# 8_MGTBank.net
KiCad netlist of a schematic drawn in Altium Designer
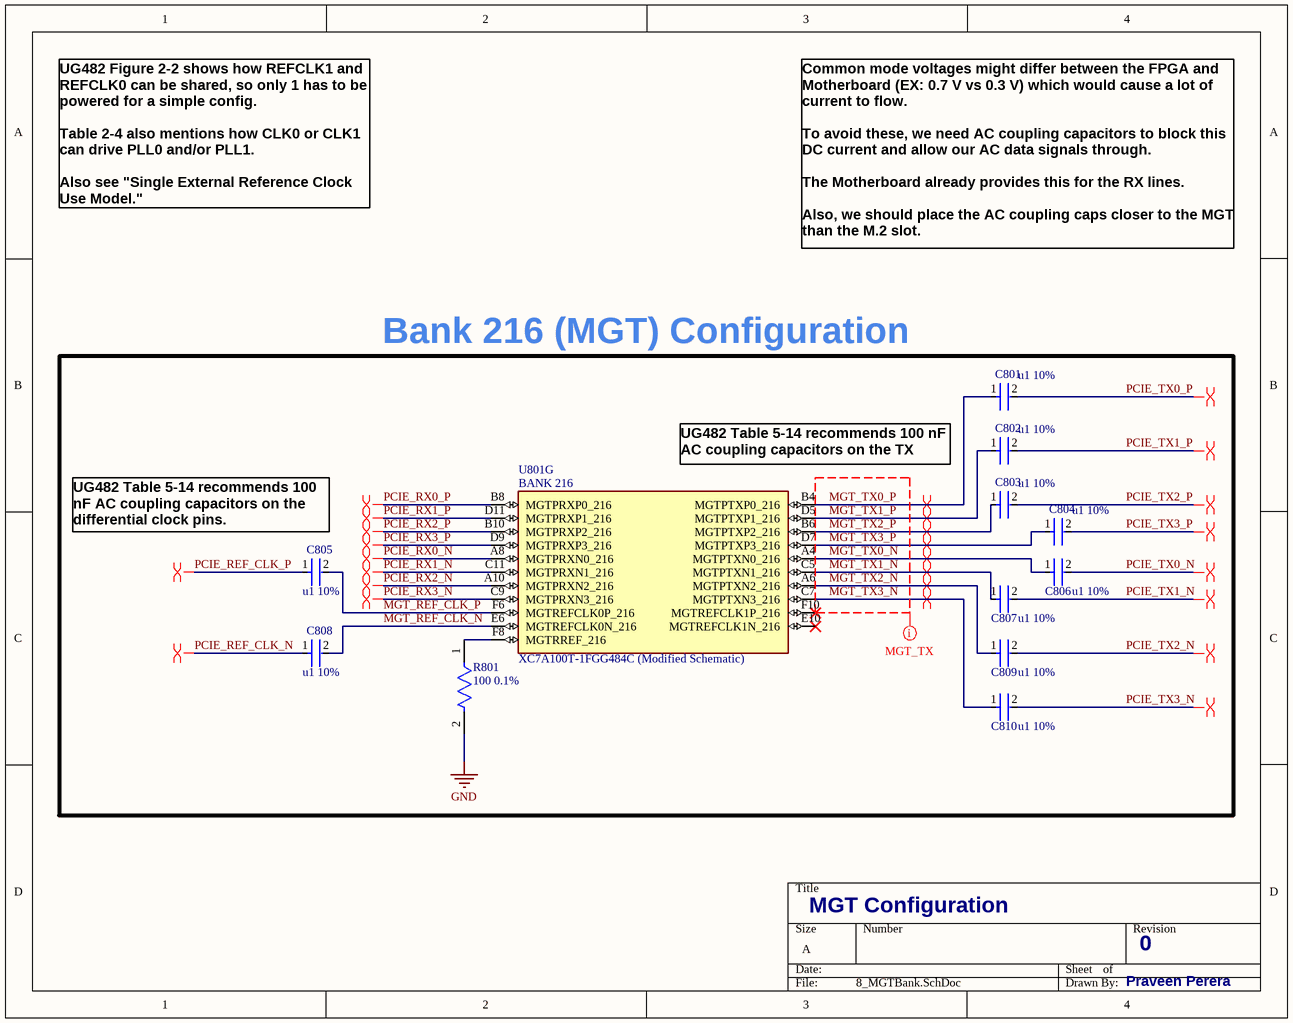
[diagram p0: 8_MGTBank.SchDoc]

(export (version "E")
  (design (tool "Eeschema 10.0.6"))
  (components
    (comp (ref "C801")
      (value "u1 10%")
      (footprint "FP-CL891-IPC_C")
      (description "CL05B104KB5NNNC\r\n\r\nCap Ceramic 100nF 50V X7R ±10% SMD 0402 +125°C Paper T/R")
      (libsource (lib "Altium Content Vault") (part "b4654b650e69147ec39a6b967a45e02"))
    )
    (comp (ref "C802")
      (value "u1 10%")
      (footprint "FP-CL891-IPC_C")
      (description "CL05B104KB5NNNC\r\n\r\nCap Ceramic 100nF 50V X7R ±10% SMD 0402 +125°C Paper T/R")
      (libsource (lib "Altium Content Vault") (part "b4654b650e69147ec39a6b967a45e02"))
    )
    (comp (ref "C803")
      (value "u1 10%")
      (footprint "FP-CL891-IPC_C")
      (description "CL05B104KB5NNNC\r\n\r\nCap Ceramic 100nF 50V X7R ±10% SMD 0402 +125°C Paper T/R")
      (libsource (lib "Altium Content Vault") (part "b4654b650e69147ec39a6b967a45e02"))
    )
    (comp (ref "C804")
      (value "u1 10%")
      (footprint "FP-CL891-IPC_C")
      (description "CL05B104KB5NNNC\r\n\r\nCap Ceramic 100nF 50V X7R ±10% SMD 0402 +125°C Paper T/R")
      (libsource (lib "Altium Content Vault") (part "b4654b650e69147ec39a6b967a45e02"))
    )
    (comp (ref "C805")
      (value "u1 10%")
      (footprint "FP-CL891-IPC_C")
      (description "CL05B104KB5NNNC\r\n\r\nCap Ceramic 100nF 50V X7R ±10% SMD 0402 +125°C Paper T/R")
      (libsource (lib "Altium Content Vault") (part "b4654b650e69147ec39a6b967a45e02"))
    )
    (comp (ref "C806")
      (value "u1 10%")
      (footprint "FP-CL891-IPC_C")
      (description "CL05B104KB5NNNC\r\n\r\nCap Ceramic 100nF 50V X7R ±10% SMD 0402 +125°C Paper T/R")
      (libsource (lib "Altium Content Vault") (part "b4654b650e69147ec39a6b967a45e02"))
    )
    (comp (ref "C807")
      (value "u1 10%")
      (footprint "FP-CL891-IPC_C")
      (description "CL05B104KB5NNNC\r\n\r\nCap Ceramic 100nF 50V X7R ±10% SMD 0402 +125°C Paper T/R")
      (libsource (lib "Altium Content Vault") (part "b4654b650e69147ec39a6b967a45e02"))
    )
    (comp (ref "C808")
      (value "u1 10%")
      (footprint "FP-CL891-IPC_C")
      (description "CL05B104KB5NNNC\r\n\r\nCap Ceramic 100nF 50V X7R ±10% SMD 0402 +125°C Paper T/R")
      (libsource (lib "Altium Content Vault") (part "b4654b650e69147ec39a6b967a45e02"))
    )
    (comp (ref "C809")
      (value "u1 10%")
      (footprint "FP-CL891-IPC_C")
      (description "CL05B104KB5NNNC\r\n\r\nCap Ceramic 100nF 50V X7R ±10% SMD 0402 +125°C Paper T/R")
      (libsource (lib "Altium Content Vault") (part "b4654b650e69147ec39a6b967a45e02"))
    )
    (comp (ref "C810")
      (value "u1 10%")
      (footprint "FP-CL891-IPC_C")
      (description "CL05B104KB5NNNC\r\n\r\nCap Ceramic 100nF 50V X7R ±10% SMD 0402 +125°C Paper T/R")
      (libsource (lib "Altium Content Vault") (part "b4654b650e69147ec39a6b967a45e02"))
    )
    (comp (ref "R801")
      (value "100 0.1%")
      (footprint "FP-ERA1A-IPC_B")
      (description "ERA-1AEB101C\r\n\r\nRES SMD 100 OHM 0.1% 1/20W 0201")
      (fields (field (name "TOLERANCE") "0.1%"))
      (libsource (lib "Altium Content Vault") (part "1029c3af85768c4190bb7ad29bc67b5"))
    )
    (comp (ref "U801")
      (value "XC7A100T-1FGG484C (Modified Schematic)")
      (footprint "BGA484C100P22X22_2300X2300X260N")
      (description "Artix-7 Field Programmable Gate Array (FPGA) IC 285 4976640 101440 484-BBGA")
      (fields (field (name "MP") "XC7A100T-1FGG484C") (field (name "MF") "Xilinx Inc."))
      (libsource (lib "Withanage Perera") (part "XC7A100T-1FGG484C"))
    )
  )
  (nets
    (net (code "1") (name "/MGT_REF_CLK_N") (class "Default")
      (node (ref "C808") (pin "2") (pinfunction "2_2") (pintype "passive"))
      (node (ref "U801") (pin "E6") (pinfunction "MGTREFCLK0N_216_E6") (pintype "bidirectional"))
    )
    (net (code "2") (name "/MGT_REF_CLK_P") (class "Default")
      (node (ref "C805") (pin "2") (pinfunction "2_2") (pintype "passive"))
      (node (ref "U801") (pin "F6") (pinfunction "MGTREFCLK0P_216_F6") (pintype "bidirectional"))
    )
    (net (code "3") (name "/MGT_TX0_N") (class "Default")
      (node (ref "C806") (pin "1") (pinfunction "1_1") (pintype "passive"))
      (node (ref "U801") (pin "A4") (pinfunction "MGTPTXN0_216_A4") (pintype "bidirectional"))
    )
    (net (code "4") (name "/MGT_TX0_P") (class "Default")
      (node (ref "C801") (pin "1") (pinfunction "1_1") (pintype "passive"))
      (node (ref "U801") (pin "B4") (pinfunction "MGTPTXP0_216_B4") (pintype "bidirectional"))
    )
    (net (code "5") (name "/MGT_TX1_N") (class "Default")
      (node (ref "C807") (pin "1") (pinfunction "1_1") (pintype "passive"))
      (node (ref "U801") (pin "C5") (pinfunction "MGTPTXN1_216_C5") (pintype "bidirectional"))
    )
    (net (code "6") (name "/MGT_TX1_P") (class "Default")
      (node (ref "C802") (pin "1") (pinfunction "1_1") (pintype "passive"))
      (node (ref "U801") (pin "D5") (pinfunction "MGTPTXP1_216_D5") (pintype "bidirectional"))
    )
    (net (code "7") (name "/MGT_TX2_N") (class "Default")
      (node (ref "C809") (pin "1") (pinfunction "1_1") (pintype "passive"))
      (node (ref "U801") (pin "A6") (pinfunction "MGTPTXN2_216_A6") (pintype "bidirectional"))
    )
    (net (code "8") (name "/MGT_TX2_P") (class "Default")
      (node (ref "C803") (pin "1") (pinfunction "1_1") (pintype "passive"))
      (node (ref "U801") (pin "B6") (pinfunction "MGTPTXP2_216_B6") (pintype "bidirectional"))
    )
    (net (code "9") (name "/MGT_TX3_N") (class "Default")
      (node (ref "C810") (pin "1") (pinfunction "1_1") (pintype "passive"))
      (node (ref "U801") (pin "C7") (pinfunction "MGTPTXN3_216_C7") (pintype "bidirectional"))
    )
    (net (code "10") (name "/MGT_TX3_P") (class "Default")
      (node (ref "C804") (pin "1") (pinfunction "1_1") (pintype "passive"))
      (node (ref "U801") (pin "D7") (pinfunction "MGTPTXP3_216_D7") (pintype "bidirectional"))
    )
    (net (code "11") (name "/PCIE_REF_CLK_N") (class "Default")
      (node (ref "C808") (pin "1") (pinfunction "1_1") (pintype "passive"))
    )
    (net (code "12") (name "/PCIE_REF_CLK_P") (class "Default")
      (node (ref "C805") (pin "1") (pinfunction "1_1") (pintype "passive"))
    )
    (net (code "13") (name "/PCIE_RX0_N") (class "Default")
      (node (ref "U801") (pin "A8") (pinfunction "MGTPRXN0_216_A8") (pintype "bidirectional"))
    )
    (net (code "14") (name "/PCIE_RX0_P") (class "Default")
      (node (ref "U801") (pin "B8") (pinfunction "MGTPRXP0_216_B8") (pintype "bidirectional"))
    )
    (net (code "15") (name "/PCIE_RX1_N") (class "Default")
      (node (ref "U801") (pin "C11") (pinfunction "MGTPRXN1_216_C11") (pintype "bidirectional"))
    )
    (net (code "16") (name "/PCIE_RX1_P") (class "Default")
      (node (ref "U801") (pin "D11") (pinfunction "MGTPRXP1_216_D11") (pintype "bidirectional"))
    )
    (net (code "17") (name "/PCIE_RX2_N") (class "Default")
      (node (ref "U801") (pin "A10") (pinfunction "MGTPRXN2_216_A10") (pintype "bidirectional"))
    )
    (net (code "18") (name "/PCIE_RX2_P") (class "Default")
      (node (ref "U801") (pin "B10") (pinfunction "MGTPRXP2_216_B10") (pintype "bidirectional"))
    )
    (net (code "19") (name "/PCIE_RX3_N") (class "Default")
      (node (ref "U801") (pin "C9") (pinfunction "MGTPRXN3_216_C9") (pintype "bidirectional"))
    )
    (net (code "20") (name "/PCIE_RX3_P") (class "Default")
      (node (ref "U801") (pin "D9") (pinfunction "MGTPRXP3_216_D9") (pintype "bidirectional"))
    )
    (net (code "21") (name "/PCIE_TX0_N") (class "Default")
      (node (ref "C806") (pin "2") (pinfunction "2_2") (pintype "passive"))
    )
    (net (code "22") (name "/PCIE_TX0_P") (class "Default")
      (node (ref "C801") (pin "2") (pinfunction "2_2") (pintype "passive"))
    )
    (net (code "23") (name "/PCIE_TX1_N") (class "Default")
      (node (ref "C807") (pin "2") (pinfunction "2_2") (pintype "passive"))
    )
    (net (code "24") (name "/PCIE_TX1_P") (class "Default")
      (node (ref "C802") (pin "2") (pinfunction "2_2") (pintype "passive"))
    )
    (net (code "25") (name "/PCIE_TX2_N") (class "Default")
      (node (ref "C809") (pin "2") (pinfunction "2_2") (pintype "passive"))
    )
    (net (code "26") (name "/PCIE_TX2_P") (class "Default")
      (node (ref "C803") (pin "2") (pinfunction "2_2") (pintype "passive"))
    )
    (net (code "27") (name "/PCIE_TX3_N") (class "Default")
      (node (ref "C810") (pin "2") (pinfunction "2_2") (pintype "passive"))
    )
    (net (code "28") (name "/PCIE_TX3_P") (class "Default")
      (node (ref "C804") (pin "2") (pinfunction "2_2") (pintype "passive"))
    )
    (net (code "29") (name "GND") (class "Default")
      (node (ref "R801") (pin "2") (pinfunction "2_2") (pintype "passive"))
    )
    (net (code "30") (name "Net-(U801G-MGTRREF_216)") (class "Default")
      (node (ref "R801") (pin "1") (pinfunction "1_1") (pintype "passive"))
      (node (ref "U801") (pin "F8") (pinfunction "MGTRREF_216_F8") (pintype "bidirectional"))
    )
    (net (code "31") (name "unconnected-(U801G-MGTREFCLK1N_216-PadE10)") (class "Default")
      (node (ref "U801") (pin "E10") (pinfunction "MGTREFCLK1N_216_E10") (pintype "bidirectional+no_connect"))
    )
    (net (code "32") (name "unconnected-(U801G-MGTREFCLK1P_216-PadF10)") (class "Default")
      (node (ref "U801") (pin "F10") (pinfunction "MGTREFCLK1P_216_F10") (pintype "bidirectional+no_connect"))
    )
  )
)
